# 06_-_Clock_Management.net
KiCad netlist of a schematic drawn in Altium Designer
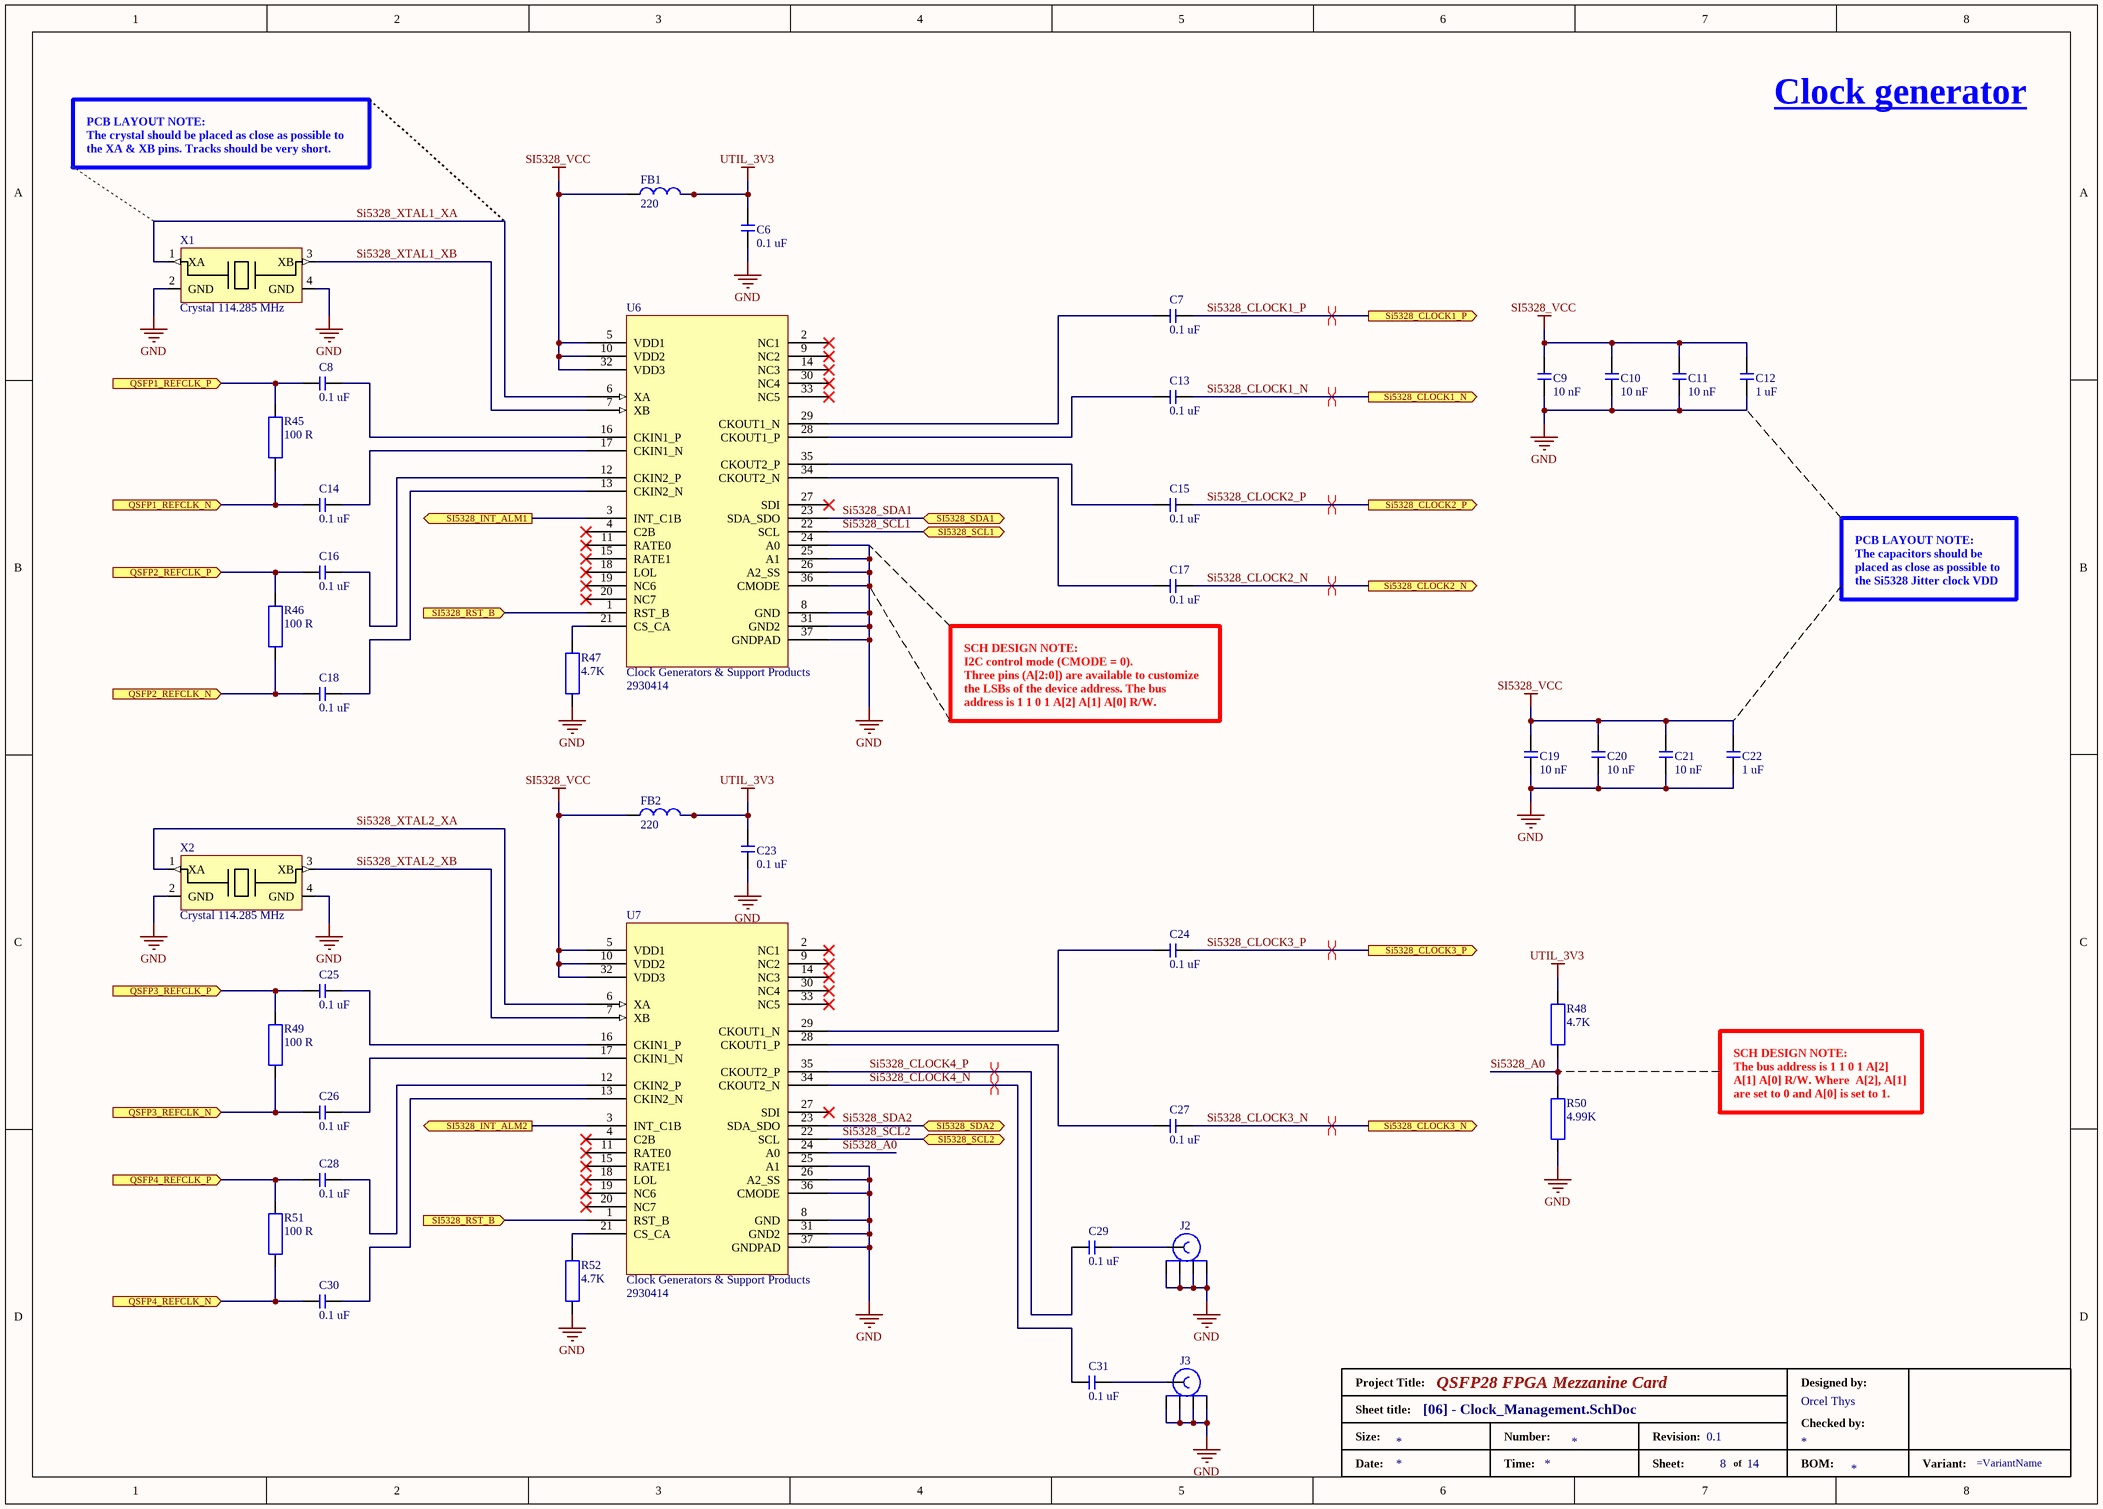
[diagram p0: [06] - Clock_Management.SchDoc]

(export (version "E")
  (design (tool "Eeschema 10.0.6"))
  (components
    (comp (ref "C6")
      (value "0.1 uF")
      (footprint "C0402")
      (description "Cap 0402 0.1 uF 50 V ±10 % Tolerance X7R Surface Mount Multilayer Ceramic Capacitor")
      (fields
        (field (name "MANUFACTURER") "Taiyo Yuden")
        (field (name "MANUFACTURER PART NUMBER") "UMK105B7104KV-FR")
      )
      (libsource (lib "QSFP28_FMC_lib") (part "UMK105B7104KV-FR"))
    )
    (comp (ref "C7")
      (value "0.1 uF")
      (footprint "C0402")
      (description "Cap 0402 0.1 uF 50 V ±10 % Tolerance X7R Surface Mount Multilayer Ceramic Capacitor")
      (fields
        (field (name "MANUFACTURER") "Taiyo Yuden")
        (field (name "MANUFACTURER PART NUMBER") "UMK105B7104KV-FR")
      )
      (libsource (lib "QSFP28_FMC_lib") (part "UMK105B7104KV-FR"))
    )
    (comp (ref "C8")
      (value "0.1 uF")
      (footprint "C0402")
      (description "Cap 0402 0.1 uF 50 V ±10 % Tolerance X7R Surface Mount Multilayer Ceramic Capacitor")
      (fields
        (field (name "MANUFACTURER") "Taiyo Yuden")
        (field (name "MANUFACTURER PART NUMBER") "UMK105B7104KV-FR")
      )
      (libsource (lib "QSFP28_FMC_lib") (part "UMK105B7104KV-FR"))
    )
    (comp (ref "C9")
      (value "10 nF")
      (footprint "C0402")
      (description "Cap Multilayer Ceramic Capacitors MLCC - SMD/SMT 25volts 10000pF X7R 10%")
      (fields
        (field (name "MANUFACTURER") "KEMET")
        (field (name "MANUFACTURER PART NUMBER") "C0402C103K3RACTU")
      )
      (libsource (lib "QSFP28_FMC_lib") (part "C0402C103K3RACTU"))
    )
    (comp (ref "C10")
      (value "10 nF")
      (footprint "C0402")
      (description "Cap Multilayer Ceramic Capacitors MLCC - SMD/SMT 25volts 10000pF X7R 10%")
      (fields
        (field (name "MANUFACTURER") "KEMET")
        (field (name "MANUFACTURER PART NUMBER") "C0402C103K3RACTU")
      )
      (libsource (lib "QSFP28_FMC_lib") (part "C0402C103K3RACTU"))
    )
    (comp (ref "C11")
      (value "10 nF")
      (footprint "C0402")
      (description "Cap Multilayer Ceramic Capacitors MLCC - SMD/SMT 25volts 10000pF X7R 10%")
      (fields
        (field (name "MANUFACTURER") "KEMET")
        (field (name "MANUFACTURER PART NUMBER") "C0402C103K3RACTU")
      )
      (libsource (lib "QSFP28_FMC_lib") (part "C0402C103K3RACTU"))
    )
    (comp (ref "C12")
      (value "1 uF")
      (footprint "C0603")
      (description "Cap Ceramic 1uF 25V X7R 10% Pad SMD 0603 125°C T/R")
      (fields
        (field (name "MANUFACTURER") "KEMET")
        (field (name "MANUFACTURER PART NUMBER") "C0603C105K3RACTU")
      )
      (libsource (lib "QSFP28_FMC_lib") (part "C0603C105K3RACTU"))
    )
    (comp (ref "C13")
      (value "0.1 uF")
      (footprint "C0402")
      (description "Cap 0402 0.1 uF 50 V ±10 % Tolerance X7R Surface Mount Multilayer Ceramic Capacitor")
      (fields
        (field (name "MANUFACTURER") "Taiyo Yuden")
        (field (name "MANUFACTURER PART NUMBER") "UMK105B7104KV-FR")
      )
      (libsource (lib "QSFP28_FMC_lib") (part "UMK105B7104KV-FR"))
    )
    (comp (ref "C14")
      (value "0.1 uF")
      (footprint "C0402")
      (description "Cap 0402 0.1 uF 50 V ±10 % Tolerance X7R Surface Mount Multilayer Ceramic Capacitor")
      (fields
        (field (name "MANUFACTURER") "Taiyo Yuden")
        (field (name "MANUFACTURER PART NUMBER") "UMK105B7104KV-FR")
      )
      (libsource (lib "QSFP28_FMC_lib") (part "UMK105B7104KV-FR"))
    )
    (comp (ref "C15")
      (value "0.1 uF")
      (footprint "C0402")
      (description "Cap 0402 0.1 uF 50 V ±10 % Tolerance X7R Surface Mount Multilayer Ceramic Capacitor")
      (fields
        (field (name "MANUFACTURER") "Taiyo Yuden")
        (field (name "MANUFACTURER PART NUMBER") "UMK105B7104KV-FR")
      )
      (libsource (lib "QSFP28_FMC_lib") (part "UMK105B7104KV-FR"))
    )
    (comp (ref "C16")
      (value "0.1 uF")
      (footprint "C0402")
      (description "Cap 0402 0.1 uF 50 V ±10 % Tolerance X7R Surface Mount Multilayer Ceramic Capacitor")
      (fields
        (field (name "MANUFACTURER") "Taiyo Yuden")
        (field (name "MANUFACTURER PART NUMBER") "UMK105B7104KV-FR")
      )
      (libsource (lib "QSFP28_FMC_lib") (part "UMK105B7104KV-FR"))
    )
    (comp (ref "C17")
      (value "0.1 uF")
      (footprint "C0402")
      (description "Cap 0402 0.1 uF 50 V ±10 % Tolerance X7R Surface Mount Multilayer Ceramic Capacitor")
      (fields
        (field (name "MANUFACTURER") "Taiyo Yuden")
        (field (name "MANUFACTURER PART NUMBER") "UMK105B7104KV-FR")
      )
      (libsource (lib "QSFP28_FMC_lib") (part "UMK105B7104KV-FR"))
    )
    (comp (ref "C18")
      (value "0.1 uF")
      (footprint "C0402")
      (description "Cap 0402 0.1 uF 50 V ±10 % Tolerance X7R Surface Mount Multilayer Ceramic Capacitor")
      (fields
        (field (name "MANUFACTURER") "Taiyo Yuden")
        (field (name "MANUFACTURER PART NUMBER") "UMK105B7104KV-FR")
      )
      (libsource (lib "QSFP28_FMC_lib") (part "UMK105B7104KV-FR"))
    )
    (comp (ref "C19")
      (value "10 nF")
      (footprint "C0402")
      (description "Cap Multilayer Ceramic Capacitors MLCC - SMD/SMT 25volts 10000pF X7R 10%")
      (fields
        (field (name "MANUFACTURER") "KEMET")
        (field (name "MANUFACTURER PART NUMBER") "C0402C103K3RACTU")
      )
      (libsource (lib "QSFP28_FMC_lib") (part "C0402C103K3RACTU"))
    )
    (comp (ref "C20")
      (value "10 nF")
      (footprint "C0402")
      (description "Cap Multilayer Ceramic Capacitors MLCC - SMD/SMT 25volts 10000pF X7R 10%")
      (fields
        (field (name "MANUFACTURER") "KEMET")
        (field (name "MANUFACTURER PART NUMBER") "C0402C103K3RACTU")
      )
      (libsource (lib "QSFP28_FMC_lib") (part "C0402C103K3RACTU"))
    )
    (comp (ref "C21")
      (value "10 nF")
      (footprint "C0402")
      (description "Cap Multilayer Ceramic Capacitors MLCC - SMD/SMT 25volts 10000pF X7R 10%")
      (fields
        (field (name "MANUFACTURER") "KEMET")
        (field (name "MANUFACTURER PART NUMBER") "C0402C103K3RACTU")
      )
      (libsource (lib "QSFP28_FMC_lib") (part "C0402C103K3RACTU"))
    )
    (comp (ref "C22")
      (value "1 uF")
      (footprint "C0603")
      (description "Cap Ceramic 1uF 25V X7R 10% Pad SMD 0603 125°C T/R")
      (fields
        (field (name "MANUFACTURER") "KEMET")
        (field (name "MANUFACTURER PART NUMBER") "C0603C105K3RACTU")
      )
      (libsource (lib "QSFP28_FMC_lib") (part "C0603C105K3RACTU"))
    )
    (comp (ref "C23")
      (value "0.1 uF")
      (footprint "C0402")
      (description "Cap 0402 0.1 uF 50 V ±10 % Tolerance X7R Surface Mount Multilayer Ceramic Capacitor")
      (fields
        (field (name "MANUFACTURER") "Taiyo Yuden")
        (field (name "MANUFACTURER PART NUMBER") "UMK105B7104KV-FR")
      )
      (libsource (lib "QSFP28_FMC_lib") (part "UMK105B7104KV-FR"))
    )
    (comp (ref "C24")
      (value "0.1 uF")
      (footprint "C0402")
      (description "Cap 0402 0.1 uF 50 V ±10 % Tolerance X7R Surface Mount Multilayer Ceramic Capacitor")
      (fields
        (field (name "MANUFACTURER") "Taiyo Yuden")
        (field (name "MANUFACTURER PART NUMBER") "UMK105B7104KV-FR")
      )
      (libsource (lib "QSFP28_FMC_lib") (part "UMK105B7104KV-FR"))
    )
    (comp (ref "C25")
      (value "0.1 uF")
      (footprint "C0402")
      (description "Cap 0402 0.1 uF 50 V ±10 % Tolerance X7R Surface Mount Multilayer Ceramic Capacitor")
      (fields
        (field (name "MANUFACTURER") "Taiyo Yuden")
        (field (name "MANUFACTURER PART NUMBER") "UMK105B7104KV-FR")
      )
      (libsource (lib "QSFP28_FMC_lib") (part "UMK105B7104KV-FR"))
    )
    (comp (ref "C26")
      (value "0.1 uF")
      (footprint "C0402")
      (description "Cap 0402 0.1 uF 50 V ±10 % Tolerance X7R Surface Mount Multilayer Ceramic Capacitor")
      (fields
        (field (name "MANUFACTURER") "Taiyo Yuden")
        (field (name "MANUFACTURER PART NUMBER") "UMK105B7104KV-FR")
      )
      (libsource (lib "QSFP28_FMC_lib") (part "UMK105B7104KV-FR"))
    )
    (comp (ref "C27")
      (value "0.1 uF")
      (footprint "C0402")
      (description "Cap 0402 0.1 uF 50 V ±10 % Tolerance X7R Surface Mount Multilayer Ceramic Capacitor")
      (fields
        (field (name "MANUFACTURER") "Taiyo Yuden")
        (field (name "MANUFACTURER PART NUMBER") "UMK105B7104KV-FR")
      )
      (libsource (lib "QSFP28_FMC_lib") (part "UMK105B7104KV-FR"))
    )
    (comp (ref "C28")
      (value "0.1 uF")
      (footprint "C0402")
      (description "Cap 0402 0.1 uF 50 V ±10 % Tolerance X7R Surface Mount Multilayer Ceramic Capacitor")
      (fields
        (field (name "MANUFACTURER") "Taiyo Yuden")
        (field (name "MANUFACTURER PART NUMBER") "UMK105B7104KV-FR")
      )
      (libsource (lib "QSFP28_FMC_lib") (part "UMK105B7104KV-FR"))
    )
    (comp (ref "C29")
      (value "0.1 uF")
      (footprint "C0402")
      (description "Cap 0402 0.1 uF 50 V ±10 % Tolerance X7R Surface Mount Multilayer Ceramic Capacitor")
      (fields
        (field (name "MANUFACTURER") "Taiyo Yuden")
        (field (name "MANUFACTURER PART NUMBER") "UMK105B7104KV-FR")
      )
      (libsource (lib "QSFP28_FMC_lib") (part "UMK105B7104KV-FR"))
    )
    (comp (ref "C30")
      (value "0.1 uF")
      (footprint "C0402")
      (description "Cap 0402 0.1 uF 50 V ±10 % Tolerance X7R Surface Mount Multilayer Ceramic Capacitor")
      (fields
        (field (name "MANUFACTURER") "Taiyo Yuden")
        (field (name "MANUFACTURER PART NUMBER") "UMK105B7104KV-FR")
      )
      (libsource (lib "QSFP28_FMC_lib") (part "UMK105B7104KV-FR"))
    )
    (comp (ref "C31")
      (value "0.1 uF")
      (footprint "C0402")
      (description "Cap 0402 0.1 uF 50 V ±10 % Tolerance X7R Surface Mount Multilayer Ceramic Capacitor")
      (fields
        (field (name "MANUFACTURER") "Taiyo Yuden")
        (field (name "MANUFACTURER PART NUMBER") "UMK105B7104KV-FR")
      )
      (libsource (lib "QSFP28_FMC_lib") (part "UMK105B7104KV-FR"))
    )
    (comp (ref "FB1")
      (value "220")
      (footprint "BEADC1608X75N")
      (description "0603 220Ω ±25% DCR=0.050Ω 2.2A")
      (fields
        (field (name "MANUFACTURER") "TDK")
        (field (name "MANUFACTURER PART NUMBER") "MPZ1608S221ATA00")
      )
      (libsource (lib "QSFP28_FMC_lib") (part "MPZ1608S221ATA00"))
    )
    (comp (ref "FB2")
      (value "220")
      (footprint "BEADC1608X75N")
      (description "0603 220Ω ±25% DCR=0.050Ω 2.2A")
      (fields
        (field (name "MANUFACTURER") "TDK")
        (field (name "MANUFACTURER PART NUMBER") "MPZ1608S221ATA00")
      )
      (libsource (lib "QSFP28_FMC_lib") (part "MPZ1608S221ATA00"))
    )
    (comp (ref "J2")
      (value "SMA-J-P-H_ST-EM1")
      (footprint "SAMTEC_SMA-J-P-H-ST-EM1")
      (description "RF Connectors / Coaxial Connectors 6 GHz, 50 Ohm SMA Jack or Plug, Cable Connector")
      (fields
        (field (name "MANUFACTURER") "Samtec")
        (field (name "MANUFACTURER PART NUMBER") "SMA-J-P-H-ST-EM1")
      )
      (libsource (lib "QSFP28_FMC_lib") (part "SMA-J-P-H-ST-EM1"))
    )
    (comp (ref "J3")
      (value "SMA-J-P-H_ST-EM1")
      (footprint "SAMTEC_SMA-J-P-H-ST-EM1")
      (description "RF Connectors / Coaxial Connectors 6 GHz, 50 Ohm SMA Jack or Plug, Cable Connector")
      (fields
        (field (name "MANUFACTURER") "Samtec")
        (field (name "MANUFACTURER PART NUMBER") "SMA-J-P-H-ST-EM1")
      )
      (libsource (lib "QSFP28_FMC_lib") (part "SMA-J-P-H-ST-EM1"))
    )
    (comp (ref "R45")
      (value "100 R")
      (footprint "R0402")
      (description "RES Thick Film 0402 100 Ohm 1% 1/10W 100ppm/C Molded SMD Punched Carrier T/R")
      (fields
        (field (name "MANUFACTURER") "Panasonic")
        (field (name "MANUFACTURER PART NUMBER") "ERJ-2RKF1000X")
      )
      (libsource (lib "QSFP28_FMC_lib") (part "ERJ-2RKF1000X"))
    )
    (comp (ref "R46")
      (value "100 R")
      (footprint "R0402")
      (description "RES Thick Film 0402 100 Ohm 1% 1/10W 100ppm/C Molded SMD Punched Carrier T/R")
      (fields
        (field (name "MANUFACTURER") "Panasonic")
        (field (name "MANUFACTURER PART NUMBER") "ERJ-2RKF1000X")
      )
      (libsource (lib "QSFP28_FMC_lib") (part "ERJ-2RKF1000X"))
    )
    (comp (ref "R47")
      (value "4.7K")
      (footprint "R0402")
      (description "RES Thick Film 0402 4.7K Ohm 1% 1/10W ±100ppm/°C Molded SMD Punched Carrier T/R")
      (fields
        (field (name "MANUFACTURER") "Panasonic")
        (field (name "MANUFACTURER PART NUMBER") "ERJ-2RKF4701X")
      )
      (libsource (lib "QSFP28_FMC_lib") (part "ERJ-2RKF4701X"))
    )
    (comp (ref "R48")
      (value "4.7K")
      (footprint "R0402")
      (description "RES Thick Film 0402 4.7K Ohm 1% 1/10W ±100ppm/°C Molded SMD Punched Carrier T/R")
      (fields
        (field (name "MANUFACTURER") "Panasonic")
        (field (name "MANUFACTURER PART NUMBER") "ERJ-2RKF4701X")
      )
      (libsource (lib "QSFP28_FMC_lib") (part "ERJ-2RKF4701X"))
    )
    (comp (ref "R49")
      (value "100 R")
      (footprint "R0402")
      (description "RES Thick Film 0402 100 Ohm 1% 1/10W 100ppm/C Molded SMD Punched Carrier T/R")
      (fields
        (field (name "MANUFACTURER") "Panasonic")
        (field (name "MANUFACTURER PART NUMBER") "ERJ-2RKF1000X")
      )
      (libsource (lib "QSFP28_FMC_lib") (part "ERJ-2RKF1000X"))
    )
    (comp (ref "R50")
      (value "4.99K")
      (footprint "R0402")
      (description "RES SMD 4.99K OHM 1% 1/10W 0402")
      (fields
        (field (name "MANUFACTURER") "Panasonic")
        (field (name "MANUFACTURER PART NUMBER") "ERJ-2RKF4991X")
      )
      (libsource (lib "QSFP28_FMC_lib") (part "ERJ-2RKF4991X"))
    )
    (comp (ref "R51")
      (value "100 R")
      (footprint "R0402")
      (description "RES Thick Film 0402 100 Ohm 1% 1/10W 100ppm/C Molded SMD Punched Carrier T/R")
      (fields
        (field (name "MANUFACTURER") "Panasonic")
        (field (name "MANUFACTURER PART NUMBER") "ERJ-2RKF1000X")
      )
      (libsource (lib "QSFP28_FMC_lib") (part "ERJ-2RKF1000X"))
    )
    (comp (ref "R52")
      (value "4.7K")
      (footprint "R0402")
      (description "RES Thick Film 0402 4.7K Ohm 1% 1/10W ±100ppm/°C Molded SMD Punched Carrier T/R")
      (fields
        (field (name "MANUFACTURER") "Panasonic")
        (field (name "MANUFACTURER PART NUMBER") "ERJ-2RKF4701X")
      )
      (libsource (lib "QSFP28_FMC_lib") (part "ERJ-2RKF4701X"))
    )
    (comp (ref "U6")
      (value "Clock Generators & Support Products")
      (footprint "QFN_50P600X600X90-37N-D")
      (description "Synchronous Ethernet Jitter Attenuating Clock Multiplier Single 0.008 MHz to 710MHz 36-Pin QFN")
      (fields
        (field (name "MANUFACTURER") "Silicon Labs")
        (field (name "MANUFACTURER PART NUMBER") "SI5328B-C-GM")
        (field (name "SUPPLIER PART NUMBER 1") "2930414")
      )
      (libsource (lib "QSFP28_FMC_lib") (part "SI5328B-C-GM"))
    )
    (comp (ref "U7")
      (value "Clock Generators & Support Products")
      (footprint "QFN_50P600X600X90-37N-D")
      (description "Synchronous Ethernet Jitter Attenuating Clock Multiplier Single 0.008 MHz to 710MHz 36-Pin QFN")
      (fields
        (field (name "MANUFACTURER") "Silicon Labs")
        (field (name "MANUFACTURER PART NUMBER") "SI5328B-C-GM")
        (field (name "SUPPLIER PART NUMBER 1") "2930414")
      )
      (libsource (lib "QSFP28_FMC_lib") (part "SI5328B-C-GM"))
    )
    (comp (ref "X1")
      (value "Crystal 114.285 MHz")
      (footprint "ABM8")
      (description "ABM8 Series 114.285 MHz ±20ppm 18pF -40 to +85 °C Ultra Miniature Ceramic Crysta")
      (fields
        (field (name "MANUFACTURER") "Abracon")
        (field (name "MANUFACTURER PART NUMBER") "ABM8-166-114.285MHZ-T2")
      )
      (libsource (lib "FmcLib") (part "ABM8-166-114.285MHZ-T2"))
    )
    (comp (ref "X2")
      (value "Crystal 114.285 MHz")
      (footprint "ABM8")
      (description "ABM8 Series 114.285 MHz ±20ppm 18pF -40 to +85 °C Ultra Miniature Ceramic Crysta")
      (fields
        (field (name "MANUFACTURER") "Abracon")
        (field (name "MANUFACTURER PART NUMBER") "ABM8-166-114.285MHZ-T2")
      )
      (libsource (lib "FmcLib") (part "ABM8-166-114.285MHZ-T2"))
    )
  )
  (nets
    (net (code "1") (name "/QSFP1_REFCLK_N") (class "Default")
      (node (ref "C14") (pin "1") (pinfunction "1_1") (pintype "passive"))
      (node (ref "R45") (pin "1") (pintype "passive"))
    )
    (net (code "2") (name "/QSFP1_REFCLK_P") (class "Default")
      (node (ref "C8") (pin "1") (pinfunction "1_1") (pintype "passive"))
      (node (ref "R45") (pin "2") (pintype "passive"))
    )
    (net (code "3") (name "/QSFP2_REFCLK_N") (class "Default")
      (node (ref "C18") (pin "1") (pinfunction "1_1") (pintype "passive"))
      (node (ref "R46") (pin "1") (pintype "passive"))
    )
    (net (code "4") (name "/QSFP2_REFCLK_P") (class "Default")
      (node (ref "C16") (pin "1") (pinfunction "1_1") (pintype "passive"))
      (node (ref "R46") (pin "2") (pintype "passive"))
    )
    (net (code "5") (name "/QSFP3_REFCLK_N") (class "Default")
      (node (ref "C26") (pin "1") (pinfunction "1_1") (pintype "passive"))
      (node (ref "R49") (pin "1") (pintype "passive"))
    )
    (net (code "6") (name "/QSFP3_REFCLK_P") (class "Default")
      (node (ref "C25") (pin "1") (pinfunction "1_1") (pintype "passive"))
      (node (ref "R49") (pin "2") (pintype "passive"))
    )
    (net (code "7") (name "/QSFP4_REFCLK_N") (class "Default")
      (node (ref "C30") (pin "1") (pinfunction "1_1") (pintype "passive"))
      (node (ref "R51") (pin "1") (pintype "passive"))
    )
    (net (code "8") (name "/QSFP4_REFCLK_P") (class "Default")
      (node (ref "C28") (pin "1") (pinfunction "1_1") (pintype "passive"))
      (node (ref "R51") (pin "2") (pintype "passive"))
    )
    (net (code "9") (name "/SI5328_INT_ALM1") (class "Default")
      (node (ref "U6") (pin "3") (pinfunction "INT_C1B_3") (pintype "passive"))
    )
    (net (code "10") (name "/SI5328_INT_ALM2") (class "Default")
      (node (ref "U7") (pin "3") (pinfunction "INT_C1B_3") (pintype "passive"))
    )
    (net (code "11") (name "/SI5328_RST_B") (class "Default")
      (node (ref "U6") (pin "1") (pinfunction "RST_B_1") (pintype "passive"))
      (node (ref "U7") (pin "1") (pinfunction "RST_B_1") (pintype "passive"))
    )
    (net (code "12") (name "/Si5328_A0") (class "Default")
      (node (ref "R48") (pin "1") (pintype "passive"))
      (node (ref "R50") (pin "2") (pintype "passive"))
      (node (ref "U7") (pin "24") (pinfunction "A0_24") (pintype "passive"))
    )
    (net (code "13") (name "/Si5328_CLOCK1_N") (class "Default")
      (node (ref "C13") (pin "2") (pinfunction "2_2") (pintype "passive"))
    )
    (net (code "14") (name "/Si5328_CLOCK1_P") (class "Default")
      (node (ref "C7") (pin "2") (pinfunction "2_2") (pintype "passive"))
    )
    (net (code "15") (name "/Si5328_CLOCK2_N") (class "Default")
      (node (ref "C17") (pin "2") (pinfunction "2_2") (pintype "passive"))
    )
    (net (code "16") (name "/Si5328_CLOCK2_P") (class "Default")
      (node (ref "C15") (pin "2") (pinfunction "2_2") (pintype "passive"))
    )
    (net (code "17") (name "/Si5328_CLOCK3_N") (class "Default")
      (node (ref "C27") (pin "2") (pinfunction "2_2") (pintype "passive"))
    )
    (net (code "18") (name "/Si5328_CLOCK3_P") (class "Default")
      (node (ref "C24") (pin "2") (pinfunction "2_2") (pintype "passive"))
    )
    (net (code "19") (name "/Si5328_CLOCK4_N") (class "Default")
      (node (ref "C31") (pin "1") (pinfunction "1_1") (pintype "passive"))
      (node (ref "U7") (pin "34") (pinfunction "CKOUT2_N_34") (pintype "passive"))
    )
    (net (code "20") (name "/Si5328_CLOCK4_P") (class "Default")
      (node (ref "C29") (pin "1") (pinfunction "1_1") (pintype "passive"))
      (node (ref "U7") (pin "35") (pinfunction "CKOUT2_P_35") (pintype "passive"))
    )
    (net (code "21") (name "/Si5328_SCL1") (class "Default")
      (node (ref "U6") (pin "22") (pinfunction "SCL_22") (pintype "passive"))
    )
    (net (code "22") (name "/Si5328_SCL2") (class "Default")
      (node (ref "U7") (pin "22") (pinfunction "SCL_22") (pintype "passive"))
    )
    (net (code "23") (name "/Si5328_SDA1") (class "Default")
      (node (ref "U6") (pin "23") (pinfunction "SDA_SDO_23") (pintype "passive"))
    )
    (net (code "24") (name "/Si5328_SDA2") (class "Default")
      (node (ref "U7") (pin "23") (pinfunction "SDA_SDO_23") (pintype "passive"))
    )
    (net (code "25") (name "/Si5328_XTAL1_XA") (class "Default")
      (node (ref "U6") (pin "6") (pinfunction "XA_6") (pintype "input"))
      (node (ref "X1") (pin "1") (pinfunction "XA_1") (pintype "output"))
    )
    (net (code "26") (name "/Si5328_XTAL1_XB") (class "Default")
      (node (ref "U6") (pin "7") (pinfunction "XB_7") (pintype "input"))
      (node (ref "X1") (pin "3") (pinfunction "XB_3") (pintype "output"))
    )
    (net (code "27") (name "/Si5328_XTAL2_XA") (class "Default")
      (node (ref "U7") (pin "6") (pinfunction "XA_6") (pintype "input"))
      (node (ref "X2") (pin "1") (pinfunction "XA_1") (pintype "output"))
    )
    (net (code "28") (name "/Si5328_XTAL2_XB") (class "Default")
      (node (ref "U7") (pin "7") (pinfunction "XB_7") (pintype "input"))
      (node (ref "X2") (pin "3") (pinfunction "XB_3") (pintype "output"))
    )
    (net (code "29") (name "GND") (class "Default")
      (node (ref "C10") (pin "1") (pinfunction "1_1") (pintype "passive"))
      (node (ref "C11") (pin "1") (pinfunction "1_1") (pintype "passive"))
      (node (ref "C12") (pin "1") (pinfunction "1_1") (pintype "passive"))
      (node (ref "C19") (pin "1") (pinfunction "1_1") (pintype "passive"))
      (node (ref "C20") (pin "1") (pinfunction "1_1") (pintype "passive"))
      (node (ref "C21") (pin "1") (pinfunction "1_1") (pintype "passive"))
      (node (ref "C22") (pin "1") (pinfunction "1_1") (pintype "passive"))
      (node (ref "C23") (pin "1") (pinfunction "1_1") (pintype "passive"))
      (node (ref "C6") (pin "1") (pinfunction "1_1") (pintype "passive"))
      (node (ref "C9") (pin "1") (pinfunction "1_1") (pintype "passive"))
      (node (ref "J2") (pin "2") (pinfunction "2_2") (pintype "passive"))
      (node (ref "J2") (pin "3") (pinfunction "3_3") (pintype "passive"))
      (node (ref "J2") (pin "4") (pinfunction "4_4") (pintype "passive"))
      (node (ref "J2") (pin "5") (pinfunction "5_5") (pintype "passive"))
      (node (ref "J3") (pin "2") (pinfunction "2_2") (pintype "passive"))
      (node (ref "J3") (pin "3") (pinfunction "3_3") (pintype "passive"))
      (node (ref "J3") (pin "4") (pinfunction "4_4") (pintype "passive"))
      (node (ref "J3") (pin "5") (pinfunction "5_5") (pintype "passive"))
      (node (ref "R47") (pin "1") (pintype "passive"))
      (node (ref "R50") (pin "1") (pintype "passive"))
      (node (ref "R52") (pin "1") (pintype "passive"))
      (node (ref "U6") (pin "24") (pinfunction "A0_24") (pintype "passive"))
      (node (ref "U6") (pin "25") (pinfunction "A1_25") (pintype "passive"))
      (node (ref "U6") (pin "26") (pinfunction "A2_SS_26") (pintype "passive"))
      (node (ref "U6") (pin "31") (pinfunction "GND2_31") (pintype "power_in"))
      (node (ref "U6") (pin "36") (pinfunction "CMODE_36") (pintype "passive"))
      (node (ref "U6") (pin "37") (pinfunction "GNDPAD_37") (pintype "power_in"))
      (node (ref "U6") (pin "8") (pinfunction "GND_8") (pintype "power_in"))
      (node (ref "U7") (pin "25") (pinfunction "A1_25") (pintype "passive"))
      (node (ref "U7") (pin "26") (pinfunction "A2_SS_26") (pintype "passive"))
      (node (ref "U7") (pin "31") (pinfunction "GND2_31") (pintype "power_in"))
      (node (ref "U7") (pin "36") (pinfunction "CMODE_36") (pintype "passive"))
      (node (ref "U7") (pin "37") (pinfunction "GNDPAD_37") (pintype "power_in"))
      (node (ref "U7") (pin "8") (pinfunction "GND_8") (pintype "power_in"))
      (node (ref "X1") (pin "2") (pinfunction "GND_2") (pintype "power_in"))
      (node (ref "X1") (pin "4") (pinfunction "GND_4") (pintype "power_in"))
      (node (ref "X2") (pin "2") (pinfunction "GND_2") (pintype "power_in"))
      (node (ref "X2") (pin "4") (pinfunction "GND_4") (pintype "power_in"))
    )
    (net (code "30") (name "Net-(C29-Pad2)") (class "Default")
      (node (ref "C29") (pin "2") (pinfunction "2_2") (pintype "passive"))
      (node (ref "J2") (pin "1") (pinfunction "1_1") (pintype "passive"))
    )
    (net (code "31") (name "Net-(C31-Pad2)") (class "Default")
      (node (ref "C31") (pin "2") (pinfunction "2_2") (pintype "passive"))
      (node (ref "J3") (pin "1") (pinfunction "1_1") (pintype "passive"))
    )
    (net (code "32") (name "Net-(U6-CKIN1_N)") (class "Default")
      (node (ref "C14") (pin "2") (pinfunction "2_2") (pintype "passive"))
      (node (ref "U6") (pin "17") (pinfunction "CKIN1_N_17") (pintype "passive"))
    )
    (net (code "33") (name "Net-(U6-CKIN1_P)") (class "Default")
      (node (ref "C8") (pin "2") (pinfunction "2_2") (pintype "passive"))
      (node (ref "U6") (pin "16") (pinfunction "CKIN1_P_16") (pintype "passive"))
    )
    (net (code "34") (name "Net-(U6-CKIN2_N)") (class "Default")
      (node (ref "C18") (pin "2") (pinfunction "2_2") (pintype "passive"))
      (node (ref "U6") (pin "13") (pinfunction "CKIN2_N_13") (pintype "passive"))
    )
    (net (code "35") (name "Net-(U6-CKIN2_P)") (class "Default")
      (node (ref "C16") (pin "2") (pinfunction "2_2") (pintype "passive"))
      (node (ref "U6") (pin "12") (pinfunction "CKIN2_P_12") (pintype "passive"))
    )
    (net (code "36") (name "Net-(U6-CKOUT1_N)") (class "Default")
      (node (ref "C7") (pin "1") (pinfunction "1_1") (pintype "passive"))
      (node (ref "U6") (pin "29") (pinfunction "CKOUT1_N_29") (pintype "passive"))
    )
    (net (code "37") (name "Net-(U6-CKOUT1_P)") (class "Default")
      (node (ref "C13") (pin "1") (pinfunction "1_1") (pintype "passive"))
      (node (ref "U6") (pin "28") (pinfunction "CKOUT1_P_28") (pintype "passive"))
    )
    (net (code "38") (name "Net-(U6-CKOUT2_N)") (class "Default")
      (node (ref "C17") (pin "1") (pinfunction "1_1") (pintype "passive"))
      (node (ref "U6") (pin "34") (pinfunction "CKOUT2_N_34") (pintype "passive"))
    )
    (net (code "39") (name "Net-(U6-CKOUT2_P)") (class "Default")
      (node (ref "C15") (pin "1") (pinfunction "1_1") (pintype "passive"))
      (node (ref "U6") (pin "35") (pinfunction "CKOUT2_P_35") (pintype "passive"))
    )
    (net (code "40") (name "Net-(U6-CS_CA)") (class "Default")
      (node (ref "R47") (pin "2") (pintype "passive"))
      (node (ref "U6") (pin "21") (pinfunction "CS_CA_21") (pintype "passive"))
    )
    (net (code "41") (name "Net-(U7-CKIN1_N)") (class "Default")
      (node (ref "C26") (pin "2") (pinfunction "2_2") (pintype "passive"))
      (node (ref "U7") (pin "17") (pinfunction "CKIN1_N_17") (pintype "passive"))
    )
    (net (code "42") (name "Net-(U7-CKIN1_P)") (class "Default")
      (node (ref "C25") (pin "2") (pinfunction "2_2") (pintype "passive"))
      (node (ref "U7") (pin "16") (pinfunction "CKIN1_P_16") (pintype "passive"))
    )
    (net (code "43") (name "Net-(U7-CKIN2_N)") (class "Default")
      (node (ref "C30") (pin "2") (pinfunction "2_2") (pintype "passive"))
      (node (ref "U7") (pin "13") (pinfunction "CKIN2_N_13") (pintype "passive"))
    )
    (net (code "44") (name "Net-(U7-CKIN2_P)") (class "Default")
      (node (ref "C28") (pin "2") (pinfunction "2_2") (pintype "passive"))
      (node (ref "U7") (pin "12") (pinfunction "CKIN2_P_12") (pintype "passive"))
    )
    (net (code "45") (name "Net-(U7-CKOUT1_N)") (class "Default")
      (node (ref "C24") (pin "1") (pinfunction "1_1") (pintype "passive"))
      (node (ref "U7") (pin "29") (pinfunction "CKOUT1_N_29") (pintype "passive"))
    )
    (net (code "46") (name "Net-(U7-CKOUT1_P)") (class "Default")
      (node (ref "C27") (pin "1") (pinfunction "1_1") (pintype "passive"))
      (node (ref "U7") (pin "28") (pinfunction "CKOUT1_P_28") (pintype "passive"))
    )
    (net (code "47") (name "Net-(U7-CS_CA)") (class "Default")
      (node (ref "R52") (pin "2") (pintype "passive"))
      (node (ref "U7") (pin "21") (pinfunction "CS_CA_21") (pintype "passive"))
    )
    (net (code "48") (name "SI5328_VCC") (class "Default")
      (node (ref "C10") (pin "2") (pinfunction "2_2") (pintype "passive"))
      (node (ref "C11") (pin "2") (pinfunction "2_2") (pintype "passive"))
      (node (ref "C12") (pin "2") (pinfunction "2_2") (pintype "passive"))
      (node (ref "C19") (pin "2") (pinfunction "2_2") (pintype "passive"))
      (node (ref "C20") (pin "2") (pinfunction "2_2") (pintype "passive"))
      (node (ref "C21") (pin "2") (pinfunction "2_2") (pintype "passive"))
      (node (ref "C22") (pin "2") (pinfunction "2_2") (pintype "passive"))
      (node (ref "C9") (pin "2") (pinfunction "2_2") (pintype "passive"))
      (node (ref "FB1") (pin "1") (pintype "passive"))
      (node (ref "FB2") (pin "1") (pintype "passive"))
      (node (ref "U6") (pin "10") (pinfunction "VDD2_10") (pintype "power_in"))
      (node (ref "U6") (pin "32") (pinfunction "VDD3_32") (pintype "power_in"))
      (node (ref "U6") (pin "5") (pinfunction "VDD1_5") (pintype "power_in"))
      (node (ref "U7") (pin "10") (pinfunction "VDD2_10") (pintype "power_in"))
      (node (ref "U7") (pin "32") (pinfunction "VDD3_32") (pintype "power_in"))
      (node (ref "U7") (pin "5") (pinfunction "VDD1_5") (pintype "power_in"))
    )
    (net (code "49") (name "UTIL_3V3") (class "Default")
      (node (ref "C23") (pin "2") (pinfunction "2_2") (pintype "passive"))
      (node (ref "C6") (pin "2") (pinfunction "2_2") (pintype "passive"))
      (node (ref "FB1") (pin "2") (pintype "passive"))
      (node (ref "FB2") (pin "2") (pintype "passive"))
      (node (ref "R48") (pin "2") (pintype "passive"))
    )
    (net (code "50") (name "unconnected-(U6-C2B-Pad4)") (class "Default")
      (node (ref "U6") (pin "4") (pinfunction "C2B_4") (pintype "passive+no_connect"))
    )
    (net (code "51") (name "unconnected-(U6-LOL-Pad18)") (class "Default")
      (node (ref "U6") (pin "18") (pinfunction "LOL_18") (pintype "passive+no_connect"))
    )
    (net (code "52") (name "unconnected-(U6-NC1-Pad2)") (class "Default")
      (node (ref "U6") (pin "2") (pinfunction "NC1_2") (pintype "passive+no_connect"))
    )
    (net (code "53") (name "unconnected-(U6-NC2-Pad9)") (class "Default")
      (node (ref "U6") (pin "9") (pinfunction "NC2_9") (pintype "passive+no_connect"))
    )
    (net (code "54") (name "unconnected-(U6-NC3-Pad14)") (class "Default")
      (node (ref "U6") (pin "14") (pinfunction "NC3_14") (pintype "passive+no_connect"))
    )
    (net (code "55") (name "unconnected-(U6-NC4-Pad30)") (class "Default")
      (node (ref "U6") (pin "30") (pinfunction "NC4_30") (pintype "passive+no_connect"))
    )
    (net (code "56") (name "unconnected-(U6-NC5-Pad33)") (class "Default")
      (node (ref "U6") (pin "33") (pinfunction "NC5_33") (pintype "passive+no_connect"))
    )
    (net (code "57") (name "unconnected-(U6-NC6-Pad19)") (class "Default")
      (node (ref "U6") (pin "19") (pinfunction "NC6_19") (pintype "passive+no_connect"))
    )
    (net (code "58") (name "unconnected-(U6-NC7-Pad20)") (class "Default")
      (node (ref "U6") (pin "20") (pinfunction "NC7_20") (pintype "passive+no_connect"))
    )
    (net (code "59") (name "unconnected-(U6-RATE0-Pad11)") (class "Default")
      (node (ref "U6") (pin "11") (pinfunction "RATE0_11") (pintype "passive+no_connect"))
    )
    (net (code "60") (name "unconnected-(U6-RATE1-Pad15)") (class "Default")
      (node (ref "U6") (pin "15") (pinfunction "RATE1_15") (pintype "passive+no_connect"))
    )
    (net (code "61") (name "unconnected-(U6-SDI-Pad27)") (class "Default")
      (node (ref "U6") (pin "27") (pinfunction "SDI_27") (pintype "passive+no_connect"))
    )
    (net (code "62") (name "unconnected-(U7-C2B-Pad4)") (class "Default")
      (node (ref "U7") (pin "4") (pinfunction "C2B_4") (pintype "passive+no_connect"))
    )
    (net (code "63") (name "unconnected-(U7-LOL-Pad18)") (class "Default")
      (node (ref "U7") (pin "18") (pinfunction "LOL_18") (pintype "passive+no_connect"))
    )
    (net (code "64") (name "unconnected-(U7-NC1-Pad2)") (class "Default")
      (node (ref "U7") (pin "2") (pinfunction "NC1_2") (pintype "passive+no_connect"))
    )
    (net (code "65") (name "unconnected-(U7-NC2-Pad9)") (class "Default")
      (node (ref "U7") (pin "9") (pinfunction "NC2_9") (pintype "passive+no_connect"))
    )
    (net (code "66") (name "unconnected-(U7-NC3-Pad14)") (class "Default")
      (node (ref "U7") (pin "14") (pinfunction "NC3_14") (pintype "passive+no_connect"))
    )
    (net (code "67") (name "unconnected-(U7-NC4-Pad30)") (class "Default")
      (node (ref "U7") (pin "30") (pinfunction "NC4_30") (pintype "passive+no_connect"))
    )
    (net (code "68") (name "unconnected-(U7-NC5-Pad33)") (class "Default")
      (node (ref "U7") (pin "33") (pinfunction "NC5_33") (pintype "passive+no_connect"))
    )
    (net (code "69") (name "unconnected-(U7-NC6-Pad19)") (class "Default")
      (node (ref "U7") (pin "19") (pinfunction "NC6_19") (pintype "passive+no_connect"))
    )
    (net (code "70") (name "unconnected-(U7-NC7-Pad20)") (class "Default")
      (node (ref "U7") (pin "20") (pinfunction "NC7_20") (pintype "passive+no_connect"))
    )
    (net (code "71") (name "unconnected-(U7-RATE0-Pad11)") (class "Default")
      (node (ref "U7") (pin "11") (pinfunction "RATE0_11") (pintype "passive+no_connect"))
    )
    (net (code "72") (name "unconnected-(U7-RATE1-Pad15)") (class "Default")
      (node (ref "U7") (pin "15") (pinfunction "RATE1_15") (pintype "passive+no_connect"))
    )
    (net (code "73") (name "unconnected-(U7-SDI-Pad27)") (class "Default")
      (node (ref "U7") (pin "27") (pinfunction "SDI_27") (pintype "passive+no_connect"))
    )
  )
)
